# SMPS_GACUN.net
KiCad netlist of a schematic drawn in EAGLE
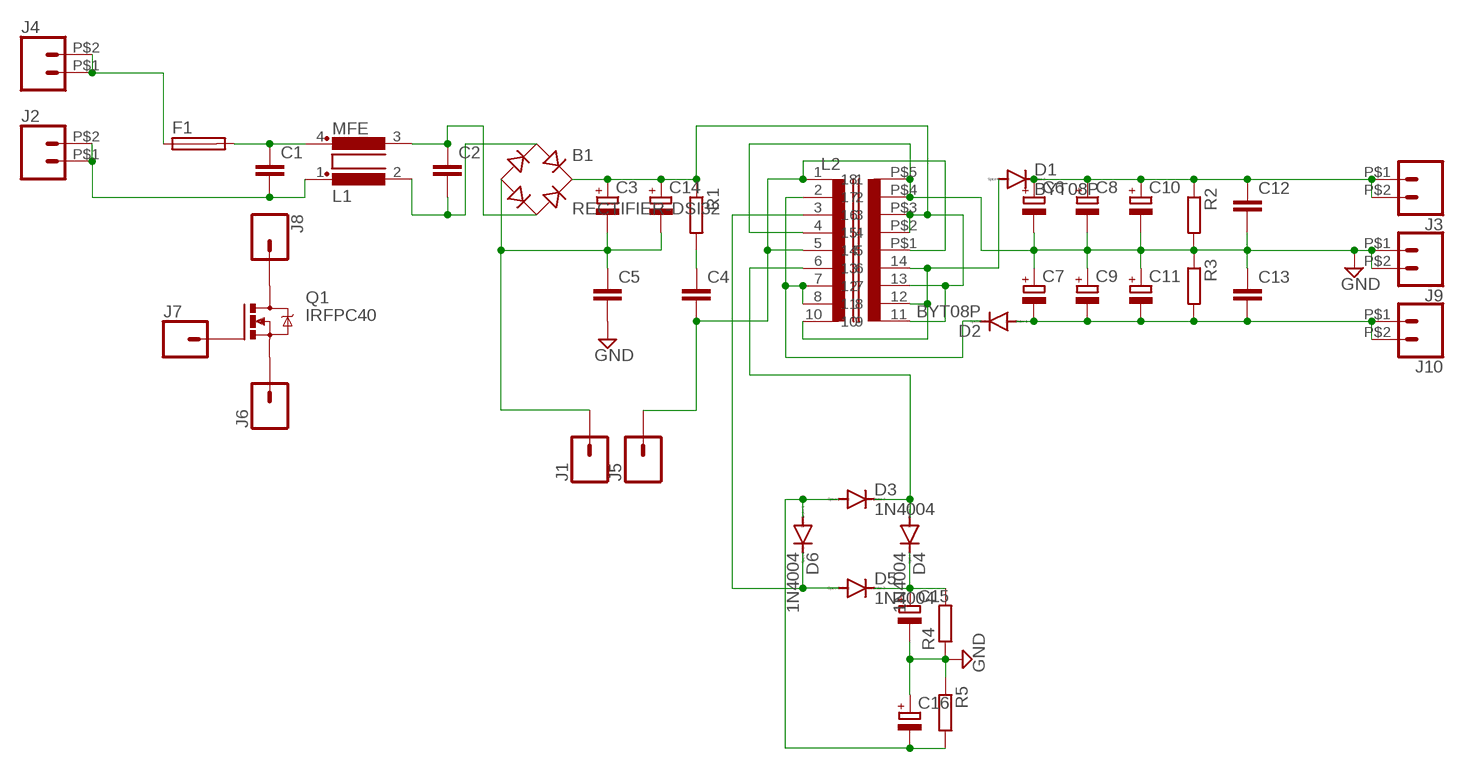
[diagram p0: schematic, sheet 1]

(export (version "E")
  (design (tool "Eeschema 10.0.6"))
  (components
    (comp (ref "B1")
      (value "RECTIFIER-DSI32")
      (footprint "eagle-import:DSI32")
      (libsource (lib "eagle-import") (part "RECTIFIER-DSI32"))
    )
    (comp (ref "C1")
      (value "C-EU225-074X268")
      (footprint "eagle-import:C225-074X268")
      (libsource (lib "eagle-import") (part "C-EU225-074X268"))
    )
    (comp (ref "C2")
      (value "C-EU225-074X268")
      (footprint "eagle-import:C225-074X268")
      (libsource (lib "eagle-import") (part "C-EU225-074X268"))
    )
    (comp (ref "C3")
      (value "CPOL-EUE10-35")
      (footprint "eagle-import:EB35D")
      (libsource (lib "eagle-import") (part "CPOL-EUE10-35"))
    )
    (comp (ref "C4")
      (value "C-EU050-025X075")
      (footprint "eagle-import:C050-025X075")
      (libsource (lib "eagle-import") (part "C-EU050-025X075"))
    )
    (comp (ref "C5")
      (value "C-EU225-074X268")
      (footprint "eagle-import:C225-074X268")
      (libsource (lib "eagle-import") (part "C-EU225-074X268"))
    )
    (comp (ref "C6")
      (value "CPOL-EUE7.5-16")
      (footprint "eagle-import:E7,5-16")
      (libsource (lib "eagle-import") (part "CPOL-EUE7.5-16"))
    )
    (comp (ref "C7")
      (value "CPOL-EUE7.5-16")
      (footprint "eagle-import:E7,5-16")
      (libsource (lib "eagle-import") (part "CPOL-EUE7.5-16"))
    )
    (comp (ref "C8")
      (value "CPOL-EUE7.5-16")
      (footprint "eagle-import:E7,5-16")
      (libsource (lib "eagle-import") (part "CPOL-EUE7.5-16"))
    )
    (comp (ref "C9")
      (value "CPOL-EUE7.5-16")
      (footprint "eagle-import:E7,5-16")
      (libsource (lib "eagle-import") (part "CPOL-EUE7.5-16"))
    )
    (comp (ref "C10")
      (value "CPOL-EUE7.5-16")
      (footprint "eagle-import:E7,5-16")
      (libsource (lib "eagle-import") (part "CPOL-EUE7.5-16"))
    )
    (comp (ref "C11")
      (value "CPOL-EUE7.5-16")
      (footprint "eagle-import:E7,5-16")
      (libsource (lib "eagle-import") (part "CPOL-EUE7.5-16"))
    )
    (comp (ref "C12")
      (value "C-EU102-043X133")
      (footprint "eagle-import:C102-043X133")
      (libsource (lib "eagle-import") (part "C-EU102-043X133"))
    )
    (comp (ref "C13")
      (value "C-EU102-043X133")
      (footprint "eagle-import:C102-043X133")
      (libsource (lib "eagle-import") (part "C-EU102-043X133"))
    )
    (comp (ref "C14")
      (value "CPOL-EUE10-35")
      (footprint "eagle-import:EB35D")
      (libsource (lib "eagle-import") (part "CPOL-EUE10-35"))
    )
    (comp (ref "C15")
      (value "CPOL-EUSANYO_F13")
      (footprint "eagle-import:SANYO-OSCON_F13")
      (libsource (lib "eagle-import") (part "CPOL-EUSANYO_F13"))
    )
    (comp (ref "C16")
      (value "CPOL-EUSANYO_F13")
      (footprint "eagle-import:SANYO-OSCON_F13")
      (libsource (lib "eagle-import") (part "CPOL-EUSANYO_F13"))
    )
    (comp (ref "D1")
      (value "BYT08P")
      (footprint "eagle-import:TO220ACS")
      (libsource (lib "eagle-import") (part "BYT08P"))
    )
    (comp (ref "D2")
      (value "BYT08P")
      (footprint "eagle-import:TO220ACS")
      (libsource (lib "eagle-import") (part "BYT08P"))
    )
    (comp (ref "D3")
      (value "1N4004")
      (footprint "eagle-import:DO41-10")
      (libsource (lib "eagle-import") (part "1N4004"))
    )
    (comp (ref "D4")
      (value "1N4004")
      (footprint "eagle-import:DO41-10")
      (libsource (lib "eagle-import") (part "1N4004"))
    )
    (comp (ref "D5")
      (value "1N4004")
      (footprint "eagle-import:DO41-10")
      (libsource (lib "eagle-import") (part "1N4004"))
    )
    (comp (ref "D6")
      (value "1N4004")
      (footprint "eagle-import:DO41-10")
      (libsource (lib "eagle-import") (part "1N4004"))
    )
    (comp (ref "F1")
      (value "SH22,5A")
      (footprint "eagle-import:SH22,5A")
      (fields (field (name "MPN") "0031.7701.11"))
      (libsource (lib "eagle-import") (part "SH22,5A"))
    )
    (comp (ref "J1")
      (value "CONN_01PTH_LONGPAD")
      (footprint "eagle-import:1X01_LONGPAD")
      (libsource (lib "eagle-import") (part "CONN_01PTH_LONGPAD"))
    )
    (comp (ref "J2")
      (value "CONN_02PTH2")
      (footprint "eagle-import:1X02_BIG")
      (libsource (lib "eagle-import") (part "CONN_02PTH2"))
    )
    (comp (ref "J3")
      (value "CONN_02PTH2")
      (footprint "eagle-import:1X02_BIG")
      (libsource (lib "eagle-import") (part "CONN_02PTH2"))
    )
    (comp (ref "J4")
      (value "CONN_02PTH2")
      (footprint "eagle-import:1X02_BIG")
      (libsource (lib "eagle-import") (part "CONN_02PTH2"))
    )
    (comp (ref "J5")
      (value "CONN_01PTH_LONGPAD")
      (footprint "eagle-import:1X01_LONGPAD")
      (libsource (lib "eagle-import") (part "CONN_01PTH_LONGPAD"))
    )
    (comp (ref "J6")
      (value "CONN_01PTH_LONGPAD")
      (footprint "eagle-import:1X01_LONGPAD")
      (libsource (lib "eagle-import") (part "CONN_01PTH_LONGPAD"))
    )
    (comp (ref "J7")
      (value "CONN_01PTH_LONGPAD")
      (footprint "eagle-import:1X01_LONGPAD")
      (libsource (lib "eagle-import") (part "CONN_01PTH_LONGPAD"))
    )
    (comp (ref "J8")
      (value "CONN_01PTH_LONGPAD")
      (footprint "eagle-import:1X01_LONGPAD")
      (libsource (lib "eagle-import") (part "CONN_01PTH_LONGPAD"))
    )
    (comp (ref "J9")
      (value "CONN_02PTH2")
      (footprint "eagle-import:1X02_BIG")
      (libsource (lib "eagle-import") (part "CONN_02PTH2"))
    )
    (comp (ref "J10")
      (value "CONN_02PTH2")
      (footprint "eagle-import:1X02_BIG")
      (libsource (lib "eagle-import") (part "CONN_02PTH2"))
    )
    (comp (ref "L1")
      (value "MFE")
      (footprint "eagle-import:MFE")
      (libsource (lib "eagle-import") (part "MFE"))
    )
    (comp (ref "L2")
      (value "ST-D4TV")
      (footprint "eagle-import:ST-D4")
      (libsource (lib "eagle-import") (part "ST-D4TV"))
    )
    (comp (ref "Q1")
      (value "IRFPC40")
      (footprint "eagle-import:TO247BV")
      (libsource (lib "eagle-import") (part "IRFPC40"))
    )
    (comp (ref "R1")
      (value "R-EU_0617/17")
      (footprint "eagle-import:0617_17")
      (libsource (lib "eagle-import") (part "R-EU_0617/17"))
    )
    (comp (ref "R2")
      (value "R-EU_0617/17")
      (footprint "eagle-import:0617_17")
      (libsource (lib "eagle-import") (part "R-EU_0617/17"))
    )
    (comp (ref "R3")
      (value "R-EU_0617/17")
      (footprint "eagle-import:0617_17")
      (libsource (lib "eagle-import") (part "R-EU_0617/17"))
    )
    (comp (ref "R4")
      (value "R-EU_0207/5V")
      (footprint "eagle-import:0207_5V")
      (libsource (lib "eagle-import") (part "resistor_R-EU_0207/5V"))
    )
    (comp (ref "R5")
      (value "R-EU_0207/5V")
      (footprint "eagle-import:0207_5V")
      (libsource (lib "eagle-import") (part "resistor_R-EU_0207/5V"))
    )
  )
  (nets
    (net (code "1") (name "GND") (class "Default")
      (node (ref "C10") (pin "-") (pinfunction "-_-") (pintype "passive"))
      (node (ref "C11") (pin "+") (pinfunction "+_+") (pintype "passive"))
      (node (ref "C12") (pin "2") (pinfunction "2_2") (pintype "passive"))
      (node (ref "C13") (pin "1") (pinfunction "1_1") (pintype "passive"))
      (node (ref "C15") (pin "-") (pinfunction "-_-") (pintype "passive"))
      (node (ref "C16") (pin "+") (pinfunction "+_+") (pintype "passive"))
      (node (ref "C5") (pin "2") (pinfunction "2_2") (pintype "passive"))
      (node (ref "C6") (pin "-") (pinfunction "-_-") (pintype "passive"))
      (node (ref "C7") (pin "+") (pinfunction "+_+") (pintype "passive"))
      (node (ref "C8") (pin "-") (pinfunction "-_-") (pintype "passive"))
      (node (ref "C9") (pin "+") (pinfunction "+_+") (pintype "passive"))
      (node (ref "J9") (pin "P$1") (pinfunction "1_P$1") (pintype "passive"))
      (node (ref "J9") (pin "P$2") (pinfunction "2_P$2") (pintype "passive"))
      (node (ref "L2") (pin "4") (pinfunction "4_4") (pintype "bidirectional"))
      (node (ref "L2") (pin "P$4") (pinfunction "17_P$4") (pintype "bidirectional"))
      (node (ref "L2") (pin "P$5") (pinfunction "18_P$5") (pintype "bidirectional"))
      (node (ref "R2") (pin "2") (pinfunction "2_2") (pintype "passive"))
      (node (ref "R3") (pin "1") (pinfunction "1_1") (pintype "passive"))
      (node (ref "R4") (pin "1") (pinfunction "1_1") (pintype "passive"))
      (node (ref "R5") (pin "1") (pinfunction "1_1") (pintype "passive"))
    )
    (net (code "2") (name "Net-(B1-Pad-)") (class "Default")
      (node (ref "B1") (pin "-") (pinfunction "-_-") (pintype "passive"))
      (node (ref "C14") (pin "-") (pinfunction "-_-") (pintype "passive"))
      (node (ref "C3") (pin "-") (pinfunction "-_-") (pintype "passive"))
      (node (ref "C5") (pin "1") (pinfunction "1_1") (pintype "passive"))
      (node (ref "J1") (pin "1") (pinfunction "1_1") (pintype "passive"))
    )
    (net (code "3") (name "Net-(B1-PadAC1)") (class "Default")
      (node (ref "B1") (pin "AC1") (pinfunction "AC1_AC1") (pintype "passive"))
      (node (ref "C2") (pin "2") (pinfunction "2_2") (pintype "passive"))
      (node (ref "L1") (pin "2") (pinfunction "2_2") (pintype "passive"))
    )
    (net (code "4") (name "Net-(C4-Pad1)") (class "Default")
      (node (ref "C4") (pin "1") (pinfunction "1_1") (pintype "passive"))
      (node (ref "R1") (pin "2") (pinfunction "2_2") (pintype "passive"))
    )
    (net (code "5") (name "Net-(C15-Pad+)") (class "Default")
      (node (ref "C15") (pin "+") (pinfunction "+_+") (pintype "passive"))
      (node (ref "D4") (pin "C") (pinfunction "C_C") (pintype "passive"))
      (node (ref "D5") (pin "C") (pinfunction "C_C") (pintype "passive"))
      (node (ref "R4") (pin "2") (pinfunction "2_2") (pintype "passive"))
    )
    (net (code "6") (name "Net-(C16-Pad-)") (class "Default")
      (node (ref "C16") (pin "-") (pinfunction "-_-") (pintype "passive"))
      (node (ref "D3") (pin "A") (pinfunction "A_A") (pintype "passive"))
      (node (ref "D6") (pin "A") (pinfunction "A_A") (pintype "passive"))
      (node (ref "R5") (pin "2") (pinfunction "2_2") (pintype "passive"))
    )
    (net (code "7") (name "Net-(D2-PadC)") (class "Default")
      (node (ref "D2") (pin "C") (pinfunction "C_C") (pintype "passive"))
      (node (ref "L2") (pin "2") (pinfunction "2_2") (pintype "bidirectional"))
      (node (ref "L2") (pin "7") (pinfunction "7_7") (pintype "bidirectional"))
      (node (ref "L2") (pin "8") (pinfunction "8_8") (pintype "bidirectional"))
    )
    (net (code "8") (name "Net-(D3-PadC)") (class "Default")
      (node (ref "D3") (pin "C") (pinfunction "C_C") (pintype "passive"))
      (node (ref "D4") (pin "A") (pinfunction "A_A") (pintype "passive"))
      (node (ref "L2") (pin "6") (pinfunction "6_6") (pintype "bidirectional"))
    )
    (net (code "9") (name "Net-(D5-PadA)") (class "Default")
      (node (ref "D5") (pin "A") (pinfunction "A_A") (pintype "passive"))
      (node (ref "D6") (pin "C") (pinfunction "C_C") (pintype "passive"))
      (node (ref "L2") (pin "3") (pinfunction "3_3") (pintype "bidirectional"))
    )
    (net (code "10") (name "Net-(J2-1)") (class "Default")
      (node (ref "C1") (pin "2") (pinfunction "2_2") (pintype "passive"))
      (node (ref "J2") (pin "P$1") (pinfunction "1_P$1") (pintype "passive"))
      (node (ref "J2") (pin "P$2") (pinfunction "2_P$2") (pintype "passive"))
      (node (ref "L1") (pin "1") (pinfunction "1_1") (pintype "passive"))
    )
    (net (code "11") (name "Net-(J3-1)") (class "Default")
      (node (ref "C10") (pin "+") (pinfunction "+_+") (pintype "passive"))
      (node (ref "C12") (pin "1") (pinfunction "1_1") (pintype "passive"))
      (node (ref "C6") (pin "+") (pinfunction "+_+") (pintype "passive"))
      (node (ref "C8") (pin "+") (pinfunction "+_+") (pintype "passive"))
      (node (ref "D1") (pin "C") (pinfunction "C_C") (pintype "passive"))
      (node (ref "J3") (pin "P$1") (pinfunction "1_P$1") (pintype "passive"))
      (node (ref "J3") (pin "P$2") (pinfunction "2_P$2") (pintype "passive"))
      (node (ref "R2") (pin "1") (pinfunction "1_1") (pintype "passive"))
    )
    (net (code "12") (name "Net-(J4-1)") (class "Default")
      (node (ref "F1") (pin "1") (pinfunction "1_1") (pintype "passive"))
      (node (ref "J4") (pin "P$1") (pinfunction "1_P$1") (pintype "passive"))
      (node (ref "J4") (pin "P$2") (pinfunction "2_P$2") (pintype "passive"))
    )
    (net (code "13") (name "Net-(J6-Pad1)") (class "Default")
      (node (ref "J6") (pin "1") (pinfunction "1_1") (pintype "passive"))
      (node (ref "Q1") (pin "S") (pinfunction "S_S") (pintype "passive"))
    )
    (net (code "14") (name "Net-(J7-Pad1)") (class "Default")
      (node (ref "J7") (pin "1") (pinfunction "1_1") (pintype "passive"))
      (node (ref "Q1") (pin "G") (pinfunction "G_G") (pintype "passive"))
    )
    (net (code "15") (name "Net-(J8-Pad1)") (class "Default")
      (node (ref "J8") (pin "1") (pinfunction "1_1") (pintype "passive"))
      (node (ref "Q1") (pin "D") (pinfunction "D_D") (pintype "passive"))
    )
    (net (code "16") (name "Net-(J10-1)") (class "Default")
      (node (ref "C11") (pin "-") (pinfunction "-_-") (pintype "passive"))
      (node (ref "C13") (pin "2") (pinfunction "2_2") (pintype "passive"))
      (node (ref "C7") (pin "-") (pinfunction "-_-") (pintype "passive"))
      (node (ref "C9") (pin "-") (pinfunction "-_-") (pintype "passive"))
      (node (ref "D2") (pin "A") (pinfunction "A_A") (pintype "passive"))
      (node (ref "J10") (pin "P$1") (pinfunction "1_P$1") (pintype "passive"))
      (node (ref "J10") (pin "P$2") (pinfunction "2_P$2") (pintype "passive"))
      (node (ref "R3") (pin "2") (pinfunction "2_2") (pintype "passive"))
    )
    (net (code "17") (name "Net-(L1-3)") (class "Default")
      (node (ref "C1") (pin "1") (pinfunction "1_1") (pintype "passive"))
      (node (ref "F1") (pin "2") (pinfunction "2_2") (pintype "passive"))
      (node (ref "L1") (pin "4") (pinfunction "3_4") (pintype "passive"))
    )
    (net (code "18") (name "Net-(L1-4)") (class "Default")
      (node (ref "B1") (pin "AC2") (pinfunction "AC2_AC2") (pintype "passive"))
      (node (ref "C2") (pin "1") (pinfunction "1_1") (pintype "passive"))
      (node (ref "L1") (pin "3") (pinfunction "4_3") (pintype "passive"))
    )
    (net (code "19") (name "Net-(L2-10)") (class "Default")
      (node (ref "B1") (pin "+") (pinfunction "+_+") (pintype "passive"))
      (node (ref "C14") (pin "+") (pinfunction "+_+") (pintype "passive"))
      (node (ref "C3") (pin "+") (pinfunction "+_+") (pintype "passive"))
      (node (ref "L2") (pin "11") (pinfunction "10_11") (pintype "bidirectional"))
      (node (ref "L2") (pin "13") (pinfunction "12_13") (pintype "bidirectional"))
      (node (ref "L2") (pin "P$2") (pinfunction "15_P$2") (pintype "bidirectional"))
      (node (ref "L2") (pin "P$3") (pinfunction "16_P$3") (pintype "bidirectional"))
      (node (ref "R1") (pin "1") (pinfunction "1_1") (pintype "passive"))
    )
    (net (code "20") (name "Net-(L2-11)") (class "Default")
      (node (ref "D1") (pin "A") (pinfunction "A_A") (pintype "passive"))
      (node (ref "L2") (pin "10") (pinfunction "9_10") (pintype "bidirectional"))
      (node (ref "L2") (pin "12") (pinfunction "11_12") (pintype "bidirectional"))
      (node (ref "L2") (pin "14") (pinfunction "13_14") (pintype "bidirectional"))
    )
    (net (code "21") (name "Net-(L2-14)") (class "Default")
      (node (ref "C4") (pin "2") (pinfunction "2_2") (pintype "passive"))
      (node (ref "J5") (pin "1") (pinfunction "1_1") (pintype "passive"))
      (node (ref "L2") (pin "1") (pinfunction "1_1") (pintype "bidirectional"))
      (node (ref "L2") (pin "5") (pinfunction "5_5") (pintype "bidirectional"))
      (node (ref "L2") (pin "P$1") (pinfunction "14_P$1") (pintype "bidirectional"))
    )
  )
)
